# CPU.net
KiCad netlist of a schematic drawn in Altium Designer
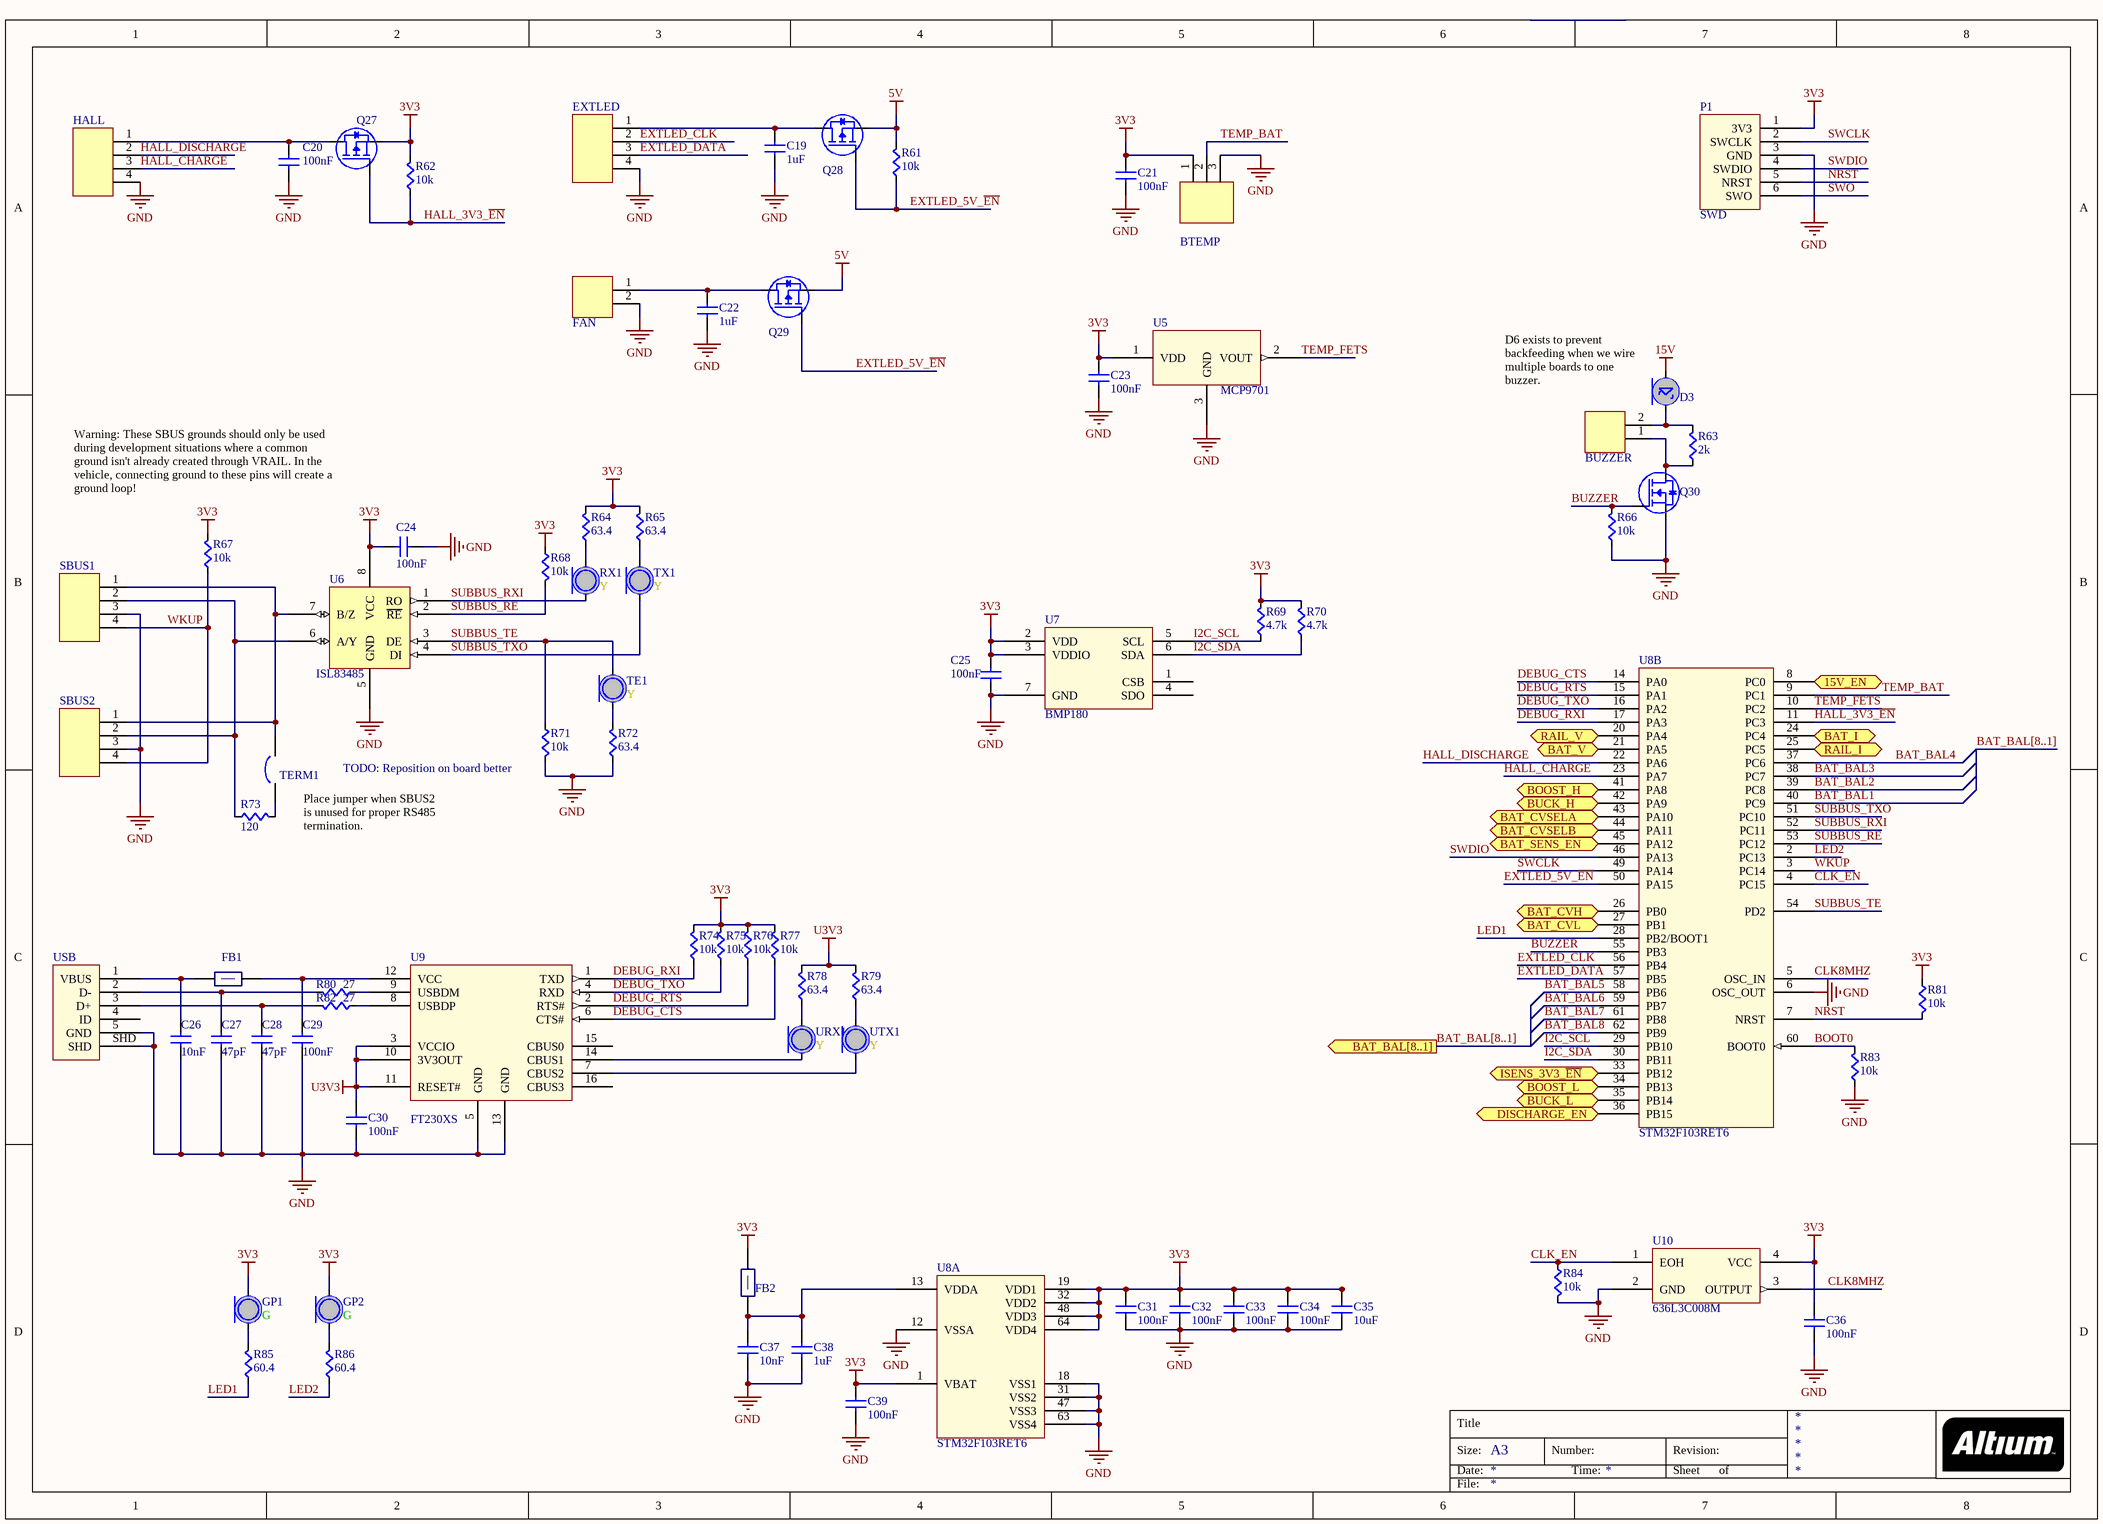
[diagram p0: CPU.SchDoc]

(export (version "E")
  (design (tool "Eeschema 10.0.6"))
  (components
    (comp (ref "BTEMP")
      (value "3pos RA sherlock connector")
      (footprint "MOLEX-HDR-1X3-SHERLOCK-RA")
      (description "Header, Molex, 2mm Pitch Sherlock Header, Single Row, Right Angle 3 Circuits, Length 3.3mm")
      (fields
        (field (name "MANUFACTURER PART NUMBER") "35363-0360")
        (field (name "MANUFACTURER") "Molex Connector Corporation")
      )
      (libsource (lib "SubjuGator8") (part "MOLEX-HDR-1x3-SHERLOCK_RA"))
    )
    (comp (ref "BUZZER")
      (value "2-pin Horz Sherlock")
      (footprint "MOLEX-HDR-1X2-SHERLOCK-HORZ")
      (fields
        (field (name "MANUFACTURER PART NUMBER") "0353630260")
        (field (name "MANUFACTURER") "Molex Inc")
      )
      (libsource (lib "SubjuGator8") (part "MOLEX-HDR-1x2-SHERLOCK_RA"))
    )
    (comp (ref "C19")
      (value "1uF")
      (footprint "CAPC0805")
      (fields (field (name "Comment") "Cap"))
      (libsource (lib "SubjuGator8") (part "Cap"))
    )
    (comp (ref "C20")
      (value "100nF")
      (footprint "CAPC0603")
      (fields (field (name "Comment") "Cap"))
      (libsource (lib "SubjuGator8") (part "Cap"))
    )
    (comp (ref "C21")
      (value "100nF")
      (footprint "CAPC0603")
      (fields (field (name "Comment") "Cap"))
      (libsource (lib "SubjuGator8") (part "Cap"))
    )
    (comp (ref "C22")
      (value "1uF")
      (footprint "CAPC0805")
      (fields (field (name "Comment") "Cap"))
      (libsource (lib "SubjuGator8") (part "Cap"))
    )
    (comp (ref "C23")
      (value "100nF")
      (footprint "CAPC0603")
      (fields (field (name "Comment") "Cap"))
      (libsource (lib "SubjuGator8") (part "Cap"))
    )
    (comp (ref "C24")
      (value "100nF")
      (footprint "CAPC0603")
      (fields (field (name "Comment") "Cap"))
      (libsource (lib "SubjuGator8") (part "Cap"))
    )
    (comp (ref "C25")
      (value "100nF")
      (footprint "CAPC0603")
      (fields (field (name "Comment") "Cap"))
      (libsource (lib "SubjuGator8") (part "Cap"))
    )
    (comp (ref "C26")
      (value "10nF")
      (footprint "CAPC0603")
      (fields (field (name "Comment") "Cap"))
      (libsource (lib "SubjuGator8") (part "Cap"))
    )
    (comp (ref "C27")
      (value "47pF")
      (footprint "CAPC0603")
      (fields (field (name "Comment") "Cap"))
      (libsource (lib "SubjuGator8") (part "Cap"))
    )
    (comp (ref "C28")
      (value "47pF")
      (footprint "CAPC0603")
      (fields (field (name "Comment") "Cap"))
      (libsource (lib "SubjuGator8") (part "Cap"))
    )
    (comp (ref "C29")
      (value "100nF")
      (footprint "CAPC0603")
      (fields (field (name "Comment") "Cap"))
      (libsource (lib "SubjuGator8") (part "Cap"))
    )
    (comp (ref "C30")
      (value "100nF")
      (footprint "CAPC0603")
      (fields (field (name "Comment") "Cap"))
      (libsource (lib "SubjuGator8") (part "Cap"))
    )
    (comp (ref "C31")
      (value "100nF")
      (footprint "CAPC0603")
      (fields (field (name "Comment") "Cap"))
      (libsource (lib "SubjuGator8") (part "Cap"))
    )
    (comp (ref "C32")
      (value "100nF")
      (footprint "CAPC0603")
      (fields (field (name "Comment") "Cap"))
      (libsource (lib "SubjuGator8") (part "Cap"))
    )
    (comp (ref "C33")
      (value "100nF")
      (footprint "CAPC0603")
      (fields (field (name "Comment") "Cap"))
      (libsource (lib "SubjuGator8") (part "Cap"))
    )
    (comp (ref "C34")
      (value "100nF")
      (footprint "CAPC0603")
      (fields (field (name "Comment") "Cap"))
      (libsource (lib "SubjuGator8") (part "Cap"))
    )
    (comp (ref "C35")
      (value "10uF")
      (footprint "CAPC0603")
      (fields (field (name "Comment") "Cap"))
      (libsource (lib "SubjuGator8") (part "Cap"))
    )
    (comp (ref "C36")
      (value "100nF")
      (footprint "CAPC0603")
      (fields (field (name "Comment") "Cap"))
      (libsource (lib "SubjuGator8") (part "Cap"))
    )
    (comp (ref "C37")
      (value "10nF")
      (footprint "CAPC0603")
      (fields (field (name "Comment") "Cap"))
      (libsource (lib "SubjuGator8") (part "Cap"))
    )
    (comp (ref "C38")
      (value "1uF")
      (footprint "CAPC0805")
      (fields (field (name "Comment") "Cap"))
      (libsource (lib "SubjuGator8") (part "Cap"))
    )
    (comp (ref "C39")
      (value "100nF")
      (footprint "CAPC0603")
      (fields (field (name "MANUFACTURER") "Kemet") (field (name "Comment") "Cap"))
      (libsource (lib "SubjuGator8") (part "Cap"))
    )
    (comp (ref "D3")
      (value "DFLS160")
      (footprint "POWERDI123")
      (description "1.0A Surface Mount Schottky Barrier Rectifier")
      (libsource (lib "SubjuGator8") (part "DFLS160"))
    )
    (comp (ref "EXTLED")
      (value "MOLEX-HDR-1x4-SHERLOCK_RA")
      (footprint "MOLEX-HDR-1X4-SHERLOCK-RA")
      (description "Header, Molex, 2mm Pitch Sherlock Header, Single Row, Horizontal, 4 Circuits, Length 3.3mm")
      (fields (field (name "MANUFACTURER PART NUMBER") "0353630460") (field (name "MANUFACTURER") "Molex"))
      (libsource (lib "SubjuGator8") (part "MOLEX-HDR-1x4-SHERLOCK_RA"))
    )
    (comp (ref "FAN")
      (value "2-pin Vert Sherlock")
      (footprint "MOLEX-HDR-1X2-SHERLOCK-VERT")
      (libsource (lib "SubjuGator8") (part "MOLEX-HDR-1x2-SHERLOCK_VERT"))
    )
    (comp (ref "FB1")
      (value "FBead")
      (footprint "RES0603")
      (description "Ferrite Bead")
      (libsource (lib "") (part "FBead_1"))
    )
    (comp (ref "FB2")
      (value "FBead")
      (footprint "RES0603")
      (description "Ferrite Bead")
      (libsource (lib "SubjuGator8") (part "FBead"))
    )
    (comp (ref "GP1")
      (value "LED")
      (footprint "LED0805")
      (fields (field (name "COLOR") "G"))
      (libsource (lib "SubjuGator8") (part "LED"))
    )
    (comp (ref "GP2")
      (value "LED")
      (footprint "LED0805")
      (fields (field (name "COLOR") "G"))
      (libsource (lib "SubjuGator8") (part "LED"))
    )
    (comp (ref "HALL")
      (value "MOLEX-HDR-1x4-SHERLOCK_VERT")
      (footprint "MOLEX-HDR-1X4-SHERLOCK-VERT")
      (libsource (lib "SubjuGator8") (part "MOLEX-HDR-1x4-SHERLOCK_VERT"))
    )
    (comp (ref "P1")
      (value "SWD")
      (footprint "SWD_STM32")
      (description "SWD connector matching the pinout on STM Discovery Boards")
      (libsource (lib "SubjuGator8") (part "SWD_STM32"))
    )
    (comp (ref "Q27")
      (value "FDN5618P")
      (footprint "PowerSOT-3")
      (description "60V P-Channel Logic Level PowerTrench MOSFET")
      (libsource (lib "SubjuGator8") (part "FDN5618P"))
    )
    (comp (ref "Q28")
      (value "FDN5618P")
      (footprint "PowerSOT-3")
      (description "60V P-Channel Logic Level PowerTrench MOSFET")
      (libsource (lib "SubjuGator8") (part "FDN5618P"))
    )
    (comp (ref "Q29")
      (value "FDN5618P")
      (footprint "PowerSOT-3")
      (description "60V P-Channel Logic Level PowerTrench MOSFET")
      (libsource (lib "SubjuGator8") (part "FDN5618P"))
    )
    (comp (ref "Q30")
      (value "FDN5630")
      (footprint "PowerSOT-3")
      (description "60V N-Channel PowerTrench MOSFET")
      (libsource (lib "SubjuGator8") (part "FDN5630"))
    )
    (comp (ref "R61")
      (value "10k")
      (footprint "RES0603")
      (fields (field (name "Comment") "Res"))
      (libsource (lib "SubjuGator8") (part "Res"))
    )
    (comp (ref "R62")
      (value "10k")
      (footprint "RES0603")
      (fields (field (name "Comment") "Res"))
      (libsource (lib "SubjuGator8") (part "Res"))
    )
    (comp (ref "R63")
      (value "2k")
      (footprint "RES0603")
      (fields (field (name "Comment") "Res"))
      (libsource (lib "SubjuGator8") (part "Res"))
    )
    (comp (ref "R64")
      (value "63.4")
      (footprint "RES0603")
      (fields (field (name "Comment") "Res"))
      (libsource (lib "SubjuGator8") (part "Res"))
    )
    (comp (ref "R65")
      (value "63.4")
      (footprint "RES0603")
      (fields (field (name "Comment") "Res"))
      (libsource (lib "SubjuGator8") (part "Res"))
    )
    (comp (ref "R66")
      (value "10k")
      (footprint "RES0603")
      (fields (field (name "Comment") "Res"))
      (libsource (lib "SubjuGator8") (part "Res"))
    )
    (comp (ref "R67")
      (value "10k")
      (footprint "RES0603")
      (fields (field (name "Comment") "Res"))
      (libsource (lib "SubjuGator8") (part "Res"))
    )
    (comp (ref "R68")
      (value "10k")
      (footprint "RES0603")
      (fields (field (name "Comment") "Res"))
      (libsource (lib "SubjuGator8") (part "Res"))
    )
    (comp (ref "R69")
      (value "4.7k")
      (footprint "RES0603")
      (fields (field (name "Comment") "Res"))
      (libsource (lib "SubjuGator8") (part "Res"))
    )
    (comp (ref "R70")
      (value "4.7k")
      (footprint "RES0603")
      (fields (field (name "Comment") "Res"))
      (libsource (lib "SubjuGator8") (part "Res"))
    )
    (comp (ref "R71")
      (value "10k")
      (footprint "RES0603")
      (fields (field (name "Comment") "Res"))
      (libsource (lib "SubjuGator8") (part "Res"))
    )
    (comp (ref "R72")
      (value "63.4")
      (footprint "RES0603")
      (fields (field (name "Comment") "Res"))
      (libsource (lib "SubjuGator8") (part "Res"))
    )
    (comp (ref "R73")
      (value "120")
      (footprint "RES0603")
      (fields (field (name "Comment") "Res"))
      (libsource (lib "SubjuGator8") (part "Res"))
    )
    (comp (ref "R74")
      (value "10k")
      (footprint "RES0603")
      (fields (field (name "Comment") "Res"))
      (libsource (lib "SubjuGator8") (part "Res"))
    )
    (comp (ref "R75")
      (value "10k")
      (footprint "RES0603")
      (fields (field (name "Comment") "Res"))
      (libsource (lib "SubjuGator8") (part "Res"))
    )
    (comp (ref "R76")
      (value "10k")
      (footprint "RES0603")
      (fields (field (name "Comment") "Res"))
      (libsource (lib "SubjuGator8") (part "Res"))
    )
    (comp (ref "R77")
      (value "10k")
      (footprint "RES0603")
      (fields (field (name "Comment") "Res"))
      (libsource (lib "SubjuGator8") (part "Res"))
    )
    (comp (ref "R78")
      (value "63.4")
      (footprint "RES0603")
      (fields (field (name "Comment") "Res"))
      (libsource (lib "SubjuGator8") (part "Res"))
    )
    (comp (ref "R79")
      (value "63.4")
      (footprint "RES0603")
      (fields (field (name "Comment") "Res"))
      (libsource (lib "SubjuGator8") (part "Res"))
    )
    (comp (ref "R80")
      (value "27")
      (footprint "RES0603")
      (fields (field (name "Comment") "Res"))
      (libsource (lib "SubjuGator8") (part "Res"))
    )
    (comp (ref "R81")
      (value "10k")
      (footprint "RES0603")
      (fields (field (name "Comment") "Res"))
      (libsource (lib "SubjuGator8") (part "Res"))
    )
    (comp (ref "R82")
      (value "27")
      (footprint "RES0603")
      (fields (field (name "Comment") "Res"))
      (libsource (lib "SubjuGator8") (part "Res"))
    )
    (comp (ref "R83")
      (value "10k")
      (footprint "RES0603")
      (fields (field (name "Comment") "Res"))
      (libsource (lib "SubjuGator8") (part "Res"))
    )
    (comp (ref "R84")
      (value "10k")
      (footprint "RES0603")
      (fields (field (name "Comment") "Res"))
      (libsource (lib "SubjuGator8") (part "Res"))
    )
    (comp (ref "R85")
      (value "60.4")
      (footprint "RES0603")
      (fields (field (name "Comment") "Res"))
      (libsource (lib "SubjuGator8") (part "Res"))
    )
    (comp (ref "R86")
      (value "60.4")
      (footprint "RES0603")
      (fields (field (name "Comment") "Res"))
      (libsource (lib "SubjuGator8") (part "Res"))
    )
    (comp (ref "RX1")
      (value "LED")
      (footprint "LED0805")
      (fields (field (name "COLOR") "Y"))
      (libsource (lib "SubjuGator8") (part "LED"))
    )
    (comp (ref "SBUS1")
      (value "MOLEX-HDR-1x4-SHERLOCK_RA")
      (footprint "MOLEX-HDR-1X4-SHERLOCK-RA")
      (description "Header, Molex, 2mm Pitch Sherlock Header, Single Row, Horizontal, 4 Circuits, Length 3.3mm")
      (fields (field (name "MANUFACTURER PART NUMBER") "0353630460") (field (name "MANUFACTURER") "Molex"))
      (libsource (lib "SubjuGator8") (part "MOLEX-HDR-1x4-SHERLOCK_RA"))
    )
    (comp (ref "SBUS2")
      (value "MOLEX-HDR-1x4-SHERLOCK_RA")
      (footprint "MOLEX-HDR-1X4-SHERLOCK-RA")
      (description "Header, Molex, 2mm Pitch Sherlock Header, Single Row, Horizontal, 4 Circuits, Length 3.3mm")
      (fields (field (name "MANUFACTURER PART NUMBER") "0353630460") (field (name "MANUFACTURER") "Molex"))
      (libsource (lib "SubjuGator8") (part "MOLEX-HDR-1x4-SHERLOCK_RA"))
    )
    (comp (ref "TE1")
      (value "LED")
      (footprint "LED0805")
      (fields (field (name "COLOR") "Y"))
      (libsource (lib "SubjuGator8") (part "LED"))
    )
    (comp (ref "TERM1")
      (value "Jumper")
      (footprint "HEADER_MALE_1X2")
      (description "Single Jumper on 1x2 Male Header")
      (libsource (lib "SubjuGator8") (part "Jumper"))
    )
    (comp (ref "TX1")
      (value "LED")
      (footprint "LED0805")
      (fields (field (name "COLOR") "Y"))
      (libsource (lib "SubjuGator8") (part "LED"))
    )
    (comp (ref "U5")
      (value "MCP9701")
      (footprint "MCP970X-E/TT")
      (description "Low-Power Linear Active Thermistor ICs")
      (libsource (lib "SubjuGator8") (part "MCP970x"))
    )
    (comp (ref "U6")
      (value "ISL83485")
      (footprint "ISL8348xIBZ")
      (description "3.3V RS485 Transceiver")
      (libsource (lib "SubjuGator8") (part "ISL83485"))
    )
    (comp (ref "U7")
      (value "BMP180")
      (footprint "BMP180")
      (description "Digital Pressure Sensor")
      (libsource (lib "SubjuGator8") (part "BMP180"))
    )
    (comp (ref "U8")
      (value "STM32F103RET6")
      (footprint "STM32F103RxTx")
      (description "Mainstream Performance line, ARM Cortex-M3 MCU")
      (libsource (lib "SubjuGator8") (part "STM32F103RET6"))
    )
    (comp (ref "U9")
      (value "FT230XS")
      (footprint "FT230XS")
      (description "USB To Basic UART IC")
      (libsource (lib "SubjuGator8") (part "FT230XS"))
    )
    (comp (ref "U10")
      (value "636L3C008M")
      (footprint "636L3C")
      (description "HCMOS/TTL Clock Oscillator")
      (libsource (lib "SubjuGator8") (part "636L3C"))
    )
    (comp (ref "URX1")
      (value "LED")
      (footprint "LED0805")
      (fields (field (name "COLOR") "Y"))
      (libsource (lib "SubjuGator8") (part "LED"))
    )
    (comp (ref "USB")
      (value "UX60SC-MB-5ST")
      (footprint "UX60SC-MB-5ST")
      (description "USB Mini B Metal Shield SMT")
      (libsource (lib "SubjuGator8") (part "UX60SC-MB-5ST"))
    )
    (comp (ref "UTX1")
      (value "LED")
      (footprint "LED0805")
      (fields (field (name "COLOR") "Y"))
      (libsource (lib "SubjuGator8") (part "LED"))
    )
  )
  (nets
    (net (code "1") (name "/15V_EN") (class "Default")
      (node (ref "U8") (pin "8") (pinfunction "PC0_8") (pintype "passive"))
    )
    (net (code "2") (name "/BAT_BAL1") (class "Default")
      (node (ref "U8") (pin "40") (pinfunction "PC9_40") (pintype "passive"))
    )
    (net (code "3") (name "/BAT_BAL2") (class "Default")
      (node (ref "U8") (pin "39") (pinfunction "PC8_39") (pintype "passive"))
    )
    (net (code "4") (name "/BAT_BAL3") (class "Default")
      (node (ref "U8") (pin "38") (pinfunction "PC7_38") (pintype "passive"))
    )
    (net (code "5") (name "/BAT_BAL4") (class "Default")
      (node (ref "U8") (pin "37") (pinfunction "PC6_37") (pintype "passive"))
    )
    (net (code "6") (name "/BAT_BAL5") (class "Default")
      (node (ref "U8") (pin "58") (pinfunction "PB6_58") (pintype "passive"))
    )
    (net (code "7") (name "/BAT_BAL6") (class "Default")
      (node (ref "U8") (pin "59") (pinfunction "PB7_59") (pintype "passive"))
    )
    (net (code "8") (name "/BAT_BAL7") (class "Default")
      (node (ref "U8") (pin "61") (pinfunction "PB8_61") (pintype "passive"))
    )
    (net (code "9") (name "/BAT_BAL8") (class "Default")
      (node (ref "U8") (pin "62") (pinfunction "PB9_62") (pintype "passive"))
    )
    (net (code "11") (name "/BAT_CVH") (class "Default")
      (node (ref "U8") (pin "26") (pinfunction "PB0_26") (pintype "passive"))
    )
    (net (code "12") (name "/BAT_CVL") (class "Default")
      (node (ref "U8") (pin "27") (pinfunction "PB1_27") (pintype "passive"))
    )
    (net (code "13") (name "/BAT_CVSELA") (class "Default")
      (node (ref "U8") (pin "43") (pinfunction "PA10_43") (pintype "passive"))
    )
    (net (code "14") (name "/BAT_CVSELB") (class "Default")
      (node (ref "U8") (pin "44") (pinfunction "PA11_44") (pintype "passive"))
    )
    (net (code "15") (name "/BAT_I") (class "Default")
      (node (ref "U8") (pin "24") (pinfunction "PC4_24") (pintype "passive"))
    )
    (net (code "16") (name "/BAT_SENS_EN") (class "Default")
      (node (ref "U8") (pin "45") (pinfunction "PA12_45") (pintype "passive"))
    )
    (net (code "17") (name "/BAT_V") (class "Default")
      (node (ref "U8") (pin "21") (pinfunction "PA5_21") (pintype "passive"))
    )
    (net (code "18") (name "/BOOST_H") (class "Default")
      (node (ref "U8") (pin "41") (pinfunction "PA8_41") (pintype "passive"))
    )
    (net (code "19") (name "/BOOST_L") (class "Default")
      (node (ref "U8") (pin "34") (pinfunction "PB13_34") (pintype "passive"))
    )
    (net (code "20") (name "/BOOT0") (class "Default")
      (node (ref "R83") (pin "1") (pinfunction "A_1") (pintype "passive"))
      (node (ref "U8") (pin "60") (pinfunction "BOOT0_60") (pintype "input"))
    )
    (net (code "21") (name "/BUCK_H") (class "Default")
      (node (ref "U8") (pin "42") (pinfunction "PA9_42") (pintype "passive"))
    )
    (net (code "22") (name "/BUCK_L") (class "Default")
      (node (ref "U8") (pin "35") (pinfunction "PB14_35") (pintype "passive"))
    )
    (net (code "23") (name "/BUZZER") (class "Default")
      (node (ref "Q30") (pin "G") (pinfunction "G_G") (pintype "passive"))
      (node (ref "R66") (pin "1") (pinfunction "A_1") (pintype "passive"))
      (node (ref "U8") (pin "55") (pinfunction "PB3_55") (pintype "passive"))
    )
    (net (code "24") (name "/CLK8MHZ") (class "Default")
      (node (ref "U10") (pin "3") (pinfunction "OUTPUT_3") (pintype "output"))
      (node (ref "U8") (pin "5") (pinfunction "OSC_IN_5") (pintype "passive"))
    )
    (net (code "25") (name "/CLK_EN") (class "Default")
      (node (ref "R84") (pin "2") (pinfunction "B_2") (pintype "passive"))
      (node (ref "U10") (pin "1") (pinfunction "EOH_1") (pintype "passive"))
      (node (ref "U8") (pin "4") (pinfunction "PC15_4") (pintype "passive"))
    )
    (net (code "26") (name "/DEBUG_CTS") (class "Default")
      (node (ref "R77") (pin "2") (pinfunction "B_2") (pintype "passive"))
      (node (ref "U8") (pin "14") (pinfunction "PA0_14") (pintype "passive"))
      (node (ref "U9") (pin "6") (pinfunction "CTS#_6") (pintype "input"))
    )
    (net (code "27") (name "/DEBUG_RTS") (class "Default")
      (node (ref "R76") (pin "2") (pinfunction "B_2") (pintype "passive"))
      (node (ref "U8") (pin "15") (pinfunction "PA1_15") (pintype "passive"))
      (node (ref "U9") (pin "2") (pinfunction "RTS#_2") (pintype "output"))
    )
    (net (code "28") (name "/DEBUG_RXI") (class "Default")
      (node (ref "R74") (pin "2") (pinfunction "B_2") (pintype "passive"))
      (node (ref "U8") (pin "17") (pinfunction "PA3_17") (pintype "passive"))
      (node (ref "U9") (pin "1") (pinfunction "TXD_1") (pintype "output"))
    )
    (net (code "29") (name "/DEBUG_TXO") (class "Default")
      (node (ref "R75") (pin "2") (pinfunction "B_2") (pintype "passive"))
      (node (ref "U8") (pin "16") (pinfunction "PA2_16") (pintype "passive"))
      (node (ref "U9") (pin "4") (pinfunction "RXD_4") (pintype "input"))
    )
    (net (code "30") (name "/DISCHARGE_EN") (class "Default")
      (node (ref "U8") (pin "36") (pinfunction "PB15_36") (pintype "passive"))
    )
    (net (code "31") (name "/EXTLED_5V_~{EN}") (class "Default")
      (node (ref "Q28") (pin "G") (pinfunction "G_G") (pintype "passive"))
      (node (ref "Q29") (pin "G") (pinfunction "G_G") (pintype "passive"))
      (node (ref "R61") (pin "2") (pinfunction "B_2") (pintype "passive"))
      (node (ref "U8") (pin "50") (pinfunction "PA15_50") (pintype "passive"))
    )
    (net (code "32") (name "/EXTLED_CLK") (class "Default")
      (node (ref "EXTLED") (pin "2") (pinfunction "2_2") (pintype "passive"))
      (node (ref "U8") (pin "56") (pinfunction "PB4_56") (pintype "passive"))
    )
    (net (code "33") (name "/EXTLED_DATA") (class "Default")
      (node (ref "EXTLED") (pin "3") (pinfunction "3_3") (pintype "passive"))
      (node (ref "U8") (pin "57") (pinfunction "PB5_57") (pintype "passive"))
    )
    (net (code "34") (name "/HALL_3V3_~{EN}") (class "Default")
      (node (ref "Q27") (pin "G") (pinfunction "G_G") (pintype "passive"))
      (node (ref "R62") (pin "2") (pinfunction "B_2") (pintype "passive"))
      (node (ref "U8") (pin "11") (pinfunction "PC3_11") (pintype "passive"))
    )
    (net (code "35") (name "/HALL_CHARGE") (class "Default")
      (node (ref "HALL") (pin "3") (pinfunction "3_3") (pintype "passive"))
      (node (ref "U8") (pin "23") (pinfunction "PA7_23") (pintype "passive"))
    )
    (net (code "36") (name "/HALL_DISCHARGE") (class "Default")
      (node (ref "HALL") (pin "2") (pinfunction "2_2") (pintype "passive"))
      (node (ref "U8") (pin "22") (pinfunction "PA6_22") (pintype "passive"))
    )
    (net (code "37") (name "/I2C_SCL") (class "Default")
      (node (ref "R69") (pin "2") (pinfunction "B_2") (pintype "passive"))
      (node (ref "U7") (pin "5") (pinfunction "SCL_5") (pintype "passive"))
      (node (ref "U8") (pin "29") (pinfunction "PB10_29") (pintype "passive"))
    )
    (net (code "38") (name "/I2C_SDA") (class "Default")
      (node (ref "R70") (pin "2") (pinfunction "B_2") (pintype "passive"))
      (node (ref "U7") (pin "6") (pinfunction "SDA_6") (pintype "passive"))
      (node (ref "U8") (pin "30") (pinfunction "PB11_30") (pintype "passive"))
    )
    (net (code "39") (name "/ISENS_3V3_~{EN}") (class "Default")
      (node (ref "U8") (pin "33") (pinfunction "PB12_33") (pintype "passive"))
    )
    (net (code "40") (name "/LED1") (class "Default")
      (node (ref "R85") (pin "2") (pinfunction "B_2") (pintype "passive"))
      (node (ref "U8") (pin "28") (pinfunction "PB2/BOOT1_28") (pintype "passive"))
    )
    (net (code "41") (name "/LED2") (class "Default")
      (node (ref "R86") (pin "2") (pinfunction "B_2") (pintype "passive"))
      (node (ref "U8") (pin "2") (pinfunction "PC13_2") (pintype "passive"))
    )
    (net (code "42") (name "/NRST") (class "Default")
      (node (ref "P1") (pin "5") (pinfunction "NRST_5") (pintype "passive"))
      (node (ref "R81") (pin "2") (pinfunction "B_2") (pintype "passive"))
      (node (ref "U8") (pin "7") (pinfunction "NRST_7") (pintype "passive"))
    )
    (net (code "43") (name "/RAIL_I") (class "Default")
      (node (ref "U8") (pin "25") (pinfunction "PC5_25") (pintype "passive"))
    )
    (net (code "44") (name "/RAIL_V") (class "Default")
      (node (ref "U8") (pin "20") (pinfunction "PA4_20") (pintype "passive"))
    )
    (net (code "45") (name "/SUBBUS_RE") (class "Default")
      (node (ref "R68") (pin "2") (pinfunction "B_2") (pintype "passive"))
      (node (ref "U6") (pin "2") (pinfunction "~{RE}_2") (pintype "input"))
      (node (ref "U8") (pin "53") (pinfunction "PC12_53") (pintype "passive"))
    )
    (net (code "46") (name "/SUBBUS_RXI") (class "Default")
      (node (ref "RX1") (pin "C") (pinfunction "C_C") (pintype "passive"))
      (node (ref "U6") (pin "1") (pinfunction "RO_1") (pintype "output"))
      (node (ref "U8") (pin "52") (pinfunction "PC11_52") (pintype "passive"))
    )
    (net (code "47") (name "/SUBBUS_TE") (class "Default")
      (node (ref "R71") (pin "1") (pinfunction "A_1") (pintype "passive"))
      (node (ref "TE1") (pin "A") (pinfunction "A_A") (pintype "passive"))
      (node (ref "U6") (pin "3") (pinfunction "DE_3") (pintype "input"))
      (node (ref "U8") (pin "54") (pinfunction "PD2_54") (pintype "passive"))
    )
    (net (code "48") (name "/SUBBUS_TXO") (class "Default")
      (node (ref "TX1") (pin "C") (pinfunction "C_C") (pintype "passive"))
      (node (ref "U6") (pin "4") (pinfunction "DI_4") (pintype "input"))
      (node (ref "U8") (pin "51") (pinfunction "PC10_51") (pintype "passive"))
    )
    (net (code "49") (name "/SWCLK") (class "Default")
      (node (ref "P1") (pin "2") (pinfunction "SWCLK_2") (pintype "passive"))
      (node (ref "U8") (pin "49") (pinfunction "PA14_49") (pintype "passive"))
    )
    (net (code "50") (name "/SWDIO") (class "Default")
      (node (ref "P1") (pin "4") (pinfunction "SWDIO_4") (pintype "passive"))
      (node (ref "U8") (pin "46") (pinfunction "PA13_46") (pintype "passive"))
    )
    (net (code "51") (name "/SWO") (class "Default")
      (node (ref "P1") (pin "6") (pinfunction "SWO_6") (pintype "passive"))
    )
    (net (code "52") (name "/TEMP_BAT") (class "Default")
      (node (ref "BTEMP") (pin "2") (pinfunction "2_2") (pintype "passive"))
      (node (ref "U8") (pin "9") (pinfunction "PC1_9") (pintype "passive"))
    )
    (net (code "53") (name "/TEMP_FETS") (class "Default")
      (node (ref "U5") (pin "2") (pinfunction "VOUT_2") (pintype "output"))
      (node (ref "U8") (pin "10") (pinfunction "PC2_10") (pintype "passive"))
    )
    (net (code "54") (name "/WKUP") (class "Default")
      (node (ref "R67") (pin "2") (pinfunction "B_2") (pintype "passive"))
      (node (ref "SBUS1") (pin "4") (pinfunction "4_4") (pintype "passive"))
      (node (ref "SBUS2") (pin "4") (pinfunction "4_4") (pintype "passive"))
      (node (ref "U8") (pin "3") (pinfunction "PC14_3") (pintype "passive"))
    )
    (net (code "55") (name "3V3") (class "Default")
      (node (ref "BTEMP") (pin "1") (pinfunction "1_1") (pintype "passive"))
      (node (ref "C21") (pin "2") (pinfunction "B_2") (pintype "passive"))
      (node (ref "C23") (pin "2") (pinfunction "B_2") (pintype "passive"))
      (node (ref "C24") (pin "2") (pinfunction "B_2") (pintype "passive"))
      (node (ref "C25") (pin "1") (pinfunction "A_1") (pintype "passive"))
      (node (ref "C31") (pin "1") (pinfunction "A_1") (pintype "passive"))
      (node (ref "C32") (pin "1") (pinfunction "A_1") (pintype "passive"))
      (node (ref "C33") (pin "1") (pinfunction "A_1") (pintype "passive"))
      (node (ref "C34") (pin "1") (pinfunction "A_1") (pintype "passive"))
      (node (ref "C35") (pin "1") (pinfunction "A_1") (pintype "passive"))
      (node (ref "C36") (pin "1") (pinfunction "A_1") (pintype "passive"))
      (node (ref "C39") (pin "1") (pinfunction "A_1") (pintype "passive"))
      (node (ref "FB2") (pin "2") (pinfunction "B_2") (pintype "passive"))
      (node (ref "GP1") (pin "A") (pinfunction "A_A") (pintype "passive"))
      (node (ref "GP2") (pin "A") (pinfunction "A_A") (pintype "passive"))
      (node (ref "P1") (pin "1") (pinfunction "3V3_1") (pintype "passive"))
      (node (ref "Q27") (pin "S") (pinfunction "S_S") (pintype "passive"))
      (node (ref "R62") (pin "1") (pinfunction "A_1") (pintype "passive"))
      (node (ref "R64") (pin "1") (pinfunction "A_1") (pintype "passive"))
      (node (ref "R65") (pin "1") (pinfunction "A_1") (pintype "passive"))
      (node (ref "R67") (pin "1") (pinfunction "A_1") (pintype "passive"))
      (node (ref "R68") (pin "1") (pinfunction "A_1") (pintype "passive"))
      (node (ref "R69") (pin "1") (pinfunction "A_1") (pintype "passive"))
      (node (ref "R70") (pin "1") (pinfunction "A_1") (pintype "passive"))
      (node (ref "R74") (pin "1") (pinfunction "A_1") (pintype "passive"))
      (node (ref "R75") (pin "1") (pinfunction "A_1") (pintype "passive"))
      (node (ref "R76") (pin "1") (pinfunction "A_1") (pintype "passive"))
      (node (ref "R77") (pin "1") (pinfunction "A_1") (pintype "passive"))
      (node (ref "R81") (pin "1") (pinfunction "A_1") (pintype "passive"))
      (node (ref "U10") (pin "4") (pinfunction "VCC_4") (pintype "power_in"))
      (node (ref "U5") (pin "1") (pinfunction "VDD_1") (pintype "power_in"))
      (node (ref "U6") (pin "8") (pinfunction "VCC_8") (pintype "power_in"))
      (node (ref "U7") (pin "2") (pinfunction "VDD_2") (pintype "power_in"))
      (node (ref "U7") (pin "3") (pinfunction "VDDIO_3") (pintype "power_in"))
      (node (ref "U8") (pin "1") (pinfunction "VBAT_1") (pintype "power_in"))
      (node (ref "U8") (pin "19") (pinfunction "VDD1_19") (pintype "power_in"))
      (node (ref "U8") (pin "32") (pinfunction "VDD2_32") (pintype "power_in"))
      (node (ref "U8") (pin "48") (pinfunction "VDD3_48") (pintype "power_in"))
      (node (ref "U8") (pin "64") (pinfunction "VDD4_64") (pintype "power_in"))
    )
    (net (code "56") (name "5V") (class "Default")
      (node (ref "Q28") (pin "S") (pinfunction "S_S") (pintype "passive"))
      (node (ref "Q29") (pin "S") (pinfunction "S_S") (pintype "passive"))
      (node (ref "R61") (pin "1") (pinfunction "A_1") (pintype "passive"))
    )
    (net (code "57") (name "15V") (class "Default")
      (node (ref "D3") (pin "A") (pinfunction "A_A") (pintype "passive"))
    )
    (net (code "58") (name "GND") (class "Default")
      (node (ref "BTEMP") (pin "3") (pinfunction "3_3") (pintype "passive"))
      (node (ref "C19") (pin "2") (pinfunction "B_2") (pintype "passive"))
      (node (ref "C20") (pin "2") (pinfunction "B_2") (pintype "passive"))
      (node (ref "C21") (pin "1") (pinfunction "A_1") (pintype "passive"))
      (node (ref "C22") (pin "2") (pinfunction "B_2") (pintype "passive"))
      (node (ref "C23") (pin "1") (pinfunction "A_1") (pintype "passive"))
      (node (ref "C24") (pin "1") (pinfunction "A_1") (pintype "passive"))
      (node (ref "C25") (pin "2") (pinfunction "B_2") (pintype "passive"))
      (node (ref "C26") (pin "2") (pinfunction "B_2") (pintype "passive"))
      (node (ref "C27") (pin "2") (pinfunction "B_2") (pintype "passive"))
      (node (ref "C28") (pin "2") (pinfunction "B_2") (pintype "passive"))
      (node (ref "C29") (pin "2") (pinfunction "B_2") (pintype "passive"))
      (node (ref "C30") (pin "2") (pinfunction "B_2") (pintype "passive"))
      (node (ref "C31") (pin "2") (pinfunction "B_2") (pintype "passive"))
      (node (ref "C32") (pin "2") (pinfunction "B_2") (pintype "passive"))
      (node (ref "C33") (pin "2") (pinfunction "B_2") (pintype "passive"))
      (node (ref "C34") (pin "2") (pinfunction "B_2") (pintype "passive"))
      (node (ref "C35") (pin "2") (pinfunction "B_2") (pintype "passive"))
      (node (ref "C36") (pin "2") (pinfunction "B_2") (pintype "passive"))
      (node (ref "C37") (pin "2") (pinfunction "B_2") (pintype "passive"))
      (node (ref "C38") (pin "2") (pinfunction "B_2") (pintype "passive"))
      (node (ref "C39") (pin "2") (pinfunction "B_2") (pintype "passive"))
      (node (ref "EXTLED") (pin "4") (pinfunction "4_4") (pintype "passive"))
      (node (ref "FAN") (pin "2") (pinfunction "2_2") (pintype "passive"))
      (node (ref "HALL") (pin "4") (pinfunction "4_4") (pintype "passive"))
      (node (ref "P1") (pin "3") (pinfunction "GND_3") (pintype "passive"))
      (node (ref "Q30") (pin "S") (pinfunction "S_S") (pintype "passive"))
      (node (ref "R66") (pin "2") (pinfunction "B_2") (pintype "passive"))
      (node (ref "R71") (pin "2") (pinfunction "B_2") (pintype "passive"))
      (node (ref "R72") (pin "2") (pinfunction "B_2") (pintype "passive"))
      (node (ref "R83") (pin "2") (pinfunction "B_2") (pintype "passive"))
      (node (ref "R84") (pin "1") (pinfunction "A_1") (pintype "passive"))
      (node (ref "SBUS1") (pin "3") (pinfunction "3_3") (pintype "passive"))
      (node (ref "SBUS2") (pin "3") (pinfunction "3_3") (pintype "passive"))
      (node (ref "U10") (pin "2") (pinfunction "GND_2") (pintype "power_in"))
      (node (ref "U5") (pin "3") (pinfunction "GND_3") (pintype "power_in"))
      (node (ref "U6") (pin "5") (pinfunction "GND_5") (pintype "power_in"))
      (node (ref "U7") (pin "7") (pinfunction "GND_7") (pintype "power_in"))
      (node (ref "U8") (pin "12") (pinfunction "VSSA_12") (pintype "power_in"))
      (node (ref "U8") (pin "18") (pinfunction "VSS1_18") (pintype "power_in"))
      (node (ref "U8") (pin "31") (pinfunction "VSS2_31") (pintype "power_in"))
      (node (ref "U8") (pin "47") (pinfunction "VSS3_47") (pintype "power_in"))
      (node (ref "U8") (pin "6") (pinfunction "OSC_OUT_6") (pintype "passive"))
      (node (ref "U8") (pin "63") (pinfunction "VSS4_63") (pintype "power_in"))
      (node (ref "U9") (pin "13") (pinfunction "GND_13") (pintype "power_in"))
      (node (ref "U9") (pin "5") (pinfunction "GND_5") (pintype "power_in"))
      (node (ref "USB") (pin "5") (pinfunction "GND_5") (pintype "passive"))
      (node (ref "USB") (pin "SHD") (pinfunction "SHD_SHD") (pintype "passive"))
    )
    (net (code "59") (name "Net-(C19-A)") (class "Default")
      (node (ref "C19") (pin "1") (pinfunction "A_1") (pintype "passive"))
      (node (ref "EXTLED") (pin "1") (pinfunction "1_1") (pintype "passive"))
      (node (ref "Q28") (pin "D") (pinfunction "D_D") (pintype "passive"))
    )
    (net (code "60") (name "Net-(C20-A)") (class "Default")
      (node (ref "C20") (pin "1") (pinfunction "A_1") (pintype "passive"))
      (node (ref "HALL") (pin "1") (pinfunction "1_1") (pintype "passive"))
      (node (ref "Q27") (pin "D") (pinfunction "D_D") (pintype "passive"))
    )
    (net (code "61") (name "Net-(C22-A)") (class "Default")
      (node (ref "C22") (pin "1") (pinfunction "A_1") (pintype "passive"))
      (node (ref "FAN") (pin "1") (pinfunction "1_1") (pintype "passive"))
      (node (ref "Q29") (pin "D") (pinfunction "D_D") (pintype "passive"))
    )
    (net (code "62") (name "Net-(C26-A)") (class "Default")
      (node (ref "C26") (pin "1") (pinfunction "A_1") (pintype "passive"))
      (node (ref "FB1") (pin "2") (pinfunction "B_2") (pintype "passive"))
      (node (ref "USB") (pin "1") (pinfunction "VBUS_1") (pintype "passive"))
    )
    (net (code "63") (name "Net-(C27-A)") (class "Default")
      (node (ref "C27") (pin "1") (pinfunction "A_1") (pintype "passive"))
      (node (ref "R80") (pin "1") (pinfunction "A_1") (pintype "passive"))
      (node (ref "USB") (pin "2") (pinfunction "D-_2") (pintype "passive"))
    )
    (net (code "64") (name "Net-(C28-A)") (class "Default")
      (node (ref "C28") (pin "1") (pinfunction "A_1") (pintype "passive"))
      (node (ref "R82") (pin "1") (pinfunction "A_1") (pintype "passive"))
      (node (ref "USB") (pin "3") (pinfunction "D+_3") (pintype "passive"))
    )
    (net (code "65") (name "Net-(C29-A)") (class "Default")
      (node (ref "C29") (pin "1") (pinfunction "A_1") (pintype "passive"))
      (node (ref "FB1") (pin "1") (pinfunction "A_1") (pintype "passive"))
      (node (ref "U9") (pin "12") (pinfunction "VCC_12") (pintype "power_in"))
    )
    (net (code "66") (name "Net-(C37-A)") (class "Default")
      (node (ref "C37") (pin "1") (pinfunction "A_1") (pintype "passive"))
      (node (ref "C38") (pin "1") (pinfunction "A_1") (pintype "passive"))
      (node (ref "FB2") (pin "1") (pinfunction "A_1") (pintype "passive"))
      (node (ref "U8") (pin "13") (pinfunction "VDDA_13") (pintype "power_in"))
    )
    (net (code "67") (name "Net-(R63-A)") (class "Default")
      (node (ref "BUZZER") (pin "2") (pinfunction "2_2") (pintype "passive"))
      (node (ref "D3") (pin "C") (pinfunction "C_C") (pintype "passive"))
      (node (ref "R63") (pin "1") (pinfunction "A_1") (pintype "passive"))
    )
    (net (code "68") (name "Net-(R63-B)") (class "Default")
      (node (ref "BUZZER") (pin "1") (pinfunction "1_1") (pintype "passive"))
      (node (ref "Q30") (pin "D") (pinfunction "D_D") (pintype "passive"))
      (node (ref "R63") (pin "2") (pinfunction "B_2") (pintype "passive"))
    )
    (net (code "69") (name "Net-(R64-B)") (class "Default")
      (node (ref "R64") (pin "2") (pinfunction "B_2") (pintype "passive"))
      (node (ref "RX1") (pin "A") (pinfunction "A_A") (pintype "passive"))
    )
    (net (code "70") (name "Net-(R65-B)") (class "Default")
      (node (ref "R65") (pin "2") (pinfunction "B_2") (pintype "passive"))
      (node (ref "TX1") (pin "A") (pinfunction "A_A") (pintype "passive"))
    )
    (net (code "71") (name "Net-(R72-A)") (class "Default")
      (node (ref "R72") (pin "1") (pinfunction "A_1") (pintype "passive"))
      (node (ref "TE1") (pin "C") (pinfunction "C_C") (pintype "passive"))
    )
    (net (code "72") (name "Net-(R73-A)") (class "Default")
      (node (ref "R73") (pin "1") (pinfunction "A_1") (pintype "passive"))
      (node (ref "TERM1") (pin "1") (pinfunction "1_1") (pintype "passive"))
    )
    (net (code "73") (name "Net-(R73-B)") (class "Default")
      (node (ref "R73") (pin "2") (pinfunction "B_2") (pintype "passive"))
      (node (ref "SBUS1") (pin "2") (pinfunction "2_2") (pintype "passive"))
      (node (ref "SBUS2") (pin "2") (pinfunction "2_2") (pintype "passive"))
      (node (ref "U6") (pin "6") (pinfunction "A/Y_6") (pintype "bidirectional"))
    )
    (net (code "74") (name "Net-(R78-B)") (class "Default")
      (node (ref "R78") (pin "2") (pinfunction "B_2") (pintype "passive"))
      (node (ref "URX1") (pin "A") (pinfunction "A_A") (pintype "passive"))
    )
    (net (code "75") (name "Net-(R79-B)") (class "Default")
      (node (ref "R79") (pin "2") (pinfunction "B_2") (pintype "passive"))
      (node (ref "UTX1") (pin "A") (pinfunction "A_A") (pintype "passive"))
    )
    (net (code "76") (name "Net-(R80-B)") (class "Default")
      (node (ref "R80") (pin "2") (pinfunction "B_2") (pintype "passive"))
      (node (ref "U9") (pin "9") (pinfunction "USBDM_9") (pintype "passive"))
    )
    (net (code "77") (name "Net-(R82-B)") (class "Default")
      (node (ref "R82") (pin "2") (pinfunction "B_2") (pintype "passive"))
      (node (ref "U9") (pin "8") (pinfunction "USBDP_8") (pintype "passive"))
    )
    (net (code "78") (name "Net-(R85-A)") (class "Default")
      (node (ref "GP1") (pin "C") (pinfunction "C_C") (pintype "passive"))
      (node (ref "R85") (pin "1") (pinfunction "A_1") (pintype "passive"))
    )
    (net (code "79") (name "Net-(R86-A)") (class "Default")
      (node (ref "GP2") (pin "C") (pinfunction "C_C") (pintype "passive"))
      (node (ref "R86") (pin "1") (pinfunction "A_1") (pintype "passive"))
    )
    (net (code "80") (name "Net-(U6-B{slash}Z)") (class "Default")
      (node (ref "SBUS1") (pin "1") (pinfunction "1_1") (pintype "passive"))
      (node (ref "SBUS2") (pin "1") (pinfunction "1_1") (pintype "passive"))
      (node (ref "TERM1") (pin "2") (pinfunction "2_2") (pintype "passive"))
      (node (ref "U6") (pin "7") (pinfunction "B/Z_7") (pintype "bidirectional"))
    )
    (net (code "81") (name "Net-(U9-CBUS1)") (class "Default")
      (node (ref "U9") (pin "14") (pinfunction "CBUS1_14") (pintype "passive"))
      (node (ref "URX1") (pin "C") (pinfunction "C_C") (pintype "passive"))
    )
    (net (code "82") (name "Net-(U9-CBUS2)") (class "Default")
      (node (ref "U9") (pin "7") (pinfunction "CBUS2_7") (pintype "passive"))
      (node (ref "UTX1") (pin "C") (pinfunction "C_C") (pintype "passive"))
    )
    (net (code "83") (name "U3V3") (class "Default")
      (node (ref "C30") (pin "1") (pinfunction "A_1") (pintype "passive"))
      (node (ref "R78") (pin "1") (pinfunction "A_1") (pintype "passive"))
      (node (ref "R79") (pin "1") (pinfunction "A_1") (pintype "passive"))
      (node (ref "U9") (pin "10") (pinfunction "3V3OUT_10") (pintype "passive"))
      (node (ref "U9") (pin "11") (pinfunction "RESET#_11") (pintype "passive"))
      (node (ref "U9") (pin "3") (pinfunction "VCCIO_3") (pintype "power_in"))
    )
    (net (code "84") (name "unconnected-(U7-CSB-Pad1)") (class "Default")
      (node (ref "U7") (pin "1") (pinfunction "CSB_1") (pintype "passive"))
    )
    (net (code "85") (name "unconnected-(U7-SDO-Pad4)") (class "Default")
      (node (ref "U7") (pin "4") (pinfunction "SDO_4") (pintype "passive"))
    )
    (net (code "86") (name "unconnected-(U9-CBUS0-Pad15)") (class "Default")
      (node (ref "U9") (pin "15") (pinfunction "CBUS0_15") (pintype "passive"))
    )
    (net (code "87") (name "unconnected-(U9-CBUS3-Pad16)") (class "Default")
      (node (ref "U9") (pin "16") (pinfunction "CBUS3_16") (pintype "passive"))
    )
    (net (code "88") (name "unconnected-(USB-ID-Pad4)") (class "Default")
      (node (ref "USB") (pin "4") (pinfunction "ID_4") (pintype "passive"))
    )
  )
)
